# G021dec.net
KiCad netlist of a schematic drawn in EAGLE
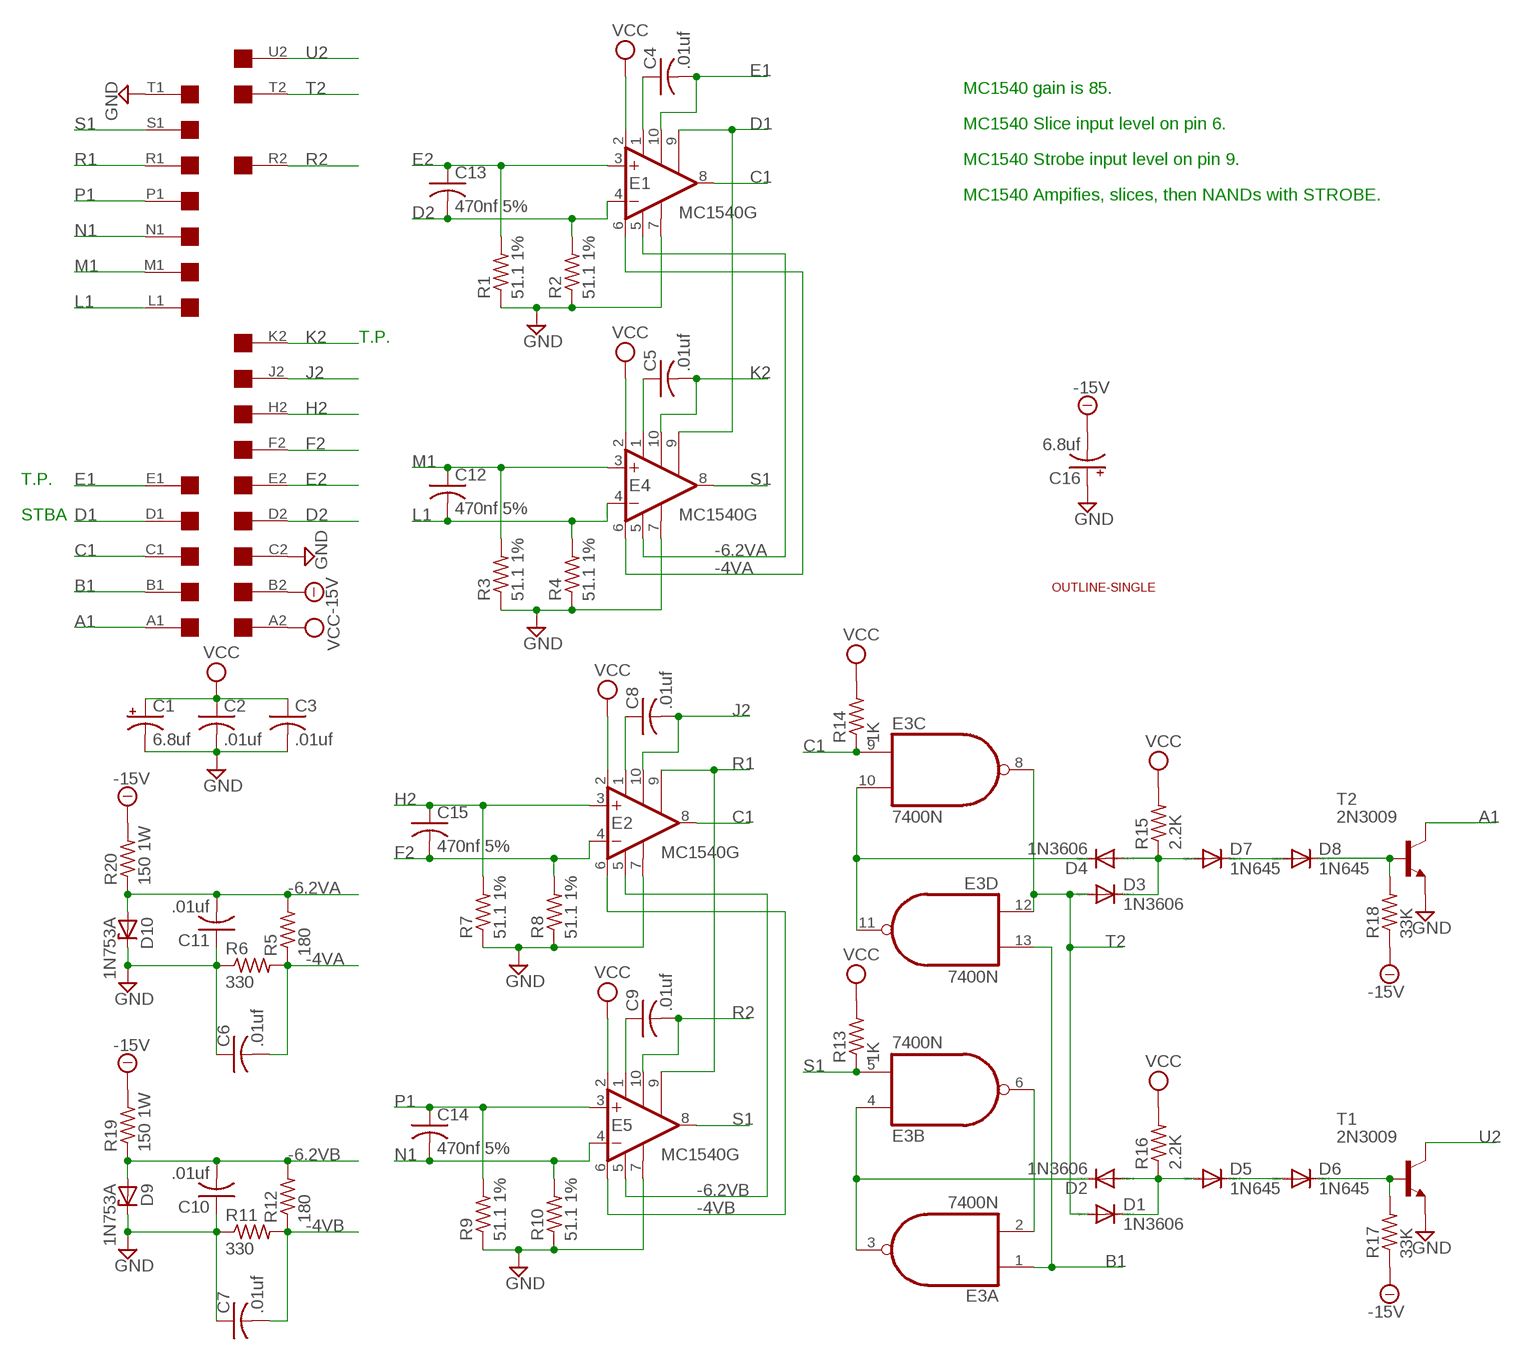
[diagram p0: schematic, sheet 1]

(export (version "E")
  (design (tool "Eeschema 10.0.6"))
  (components
    (comp (ref "C1")
      (value "6.8uf")
      (footprint "eagle-import:E15-5")
      (libsource (lib "eagle-import") (part "CPOL-USE15-5AXIAL"))
    )
    (comp (ref "C2")
      (value ".01uf")
      (footprint "eagle-import:C050-025X075")
      (libsource (lib "eagle-import") (part "C-US050-025X075"))
    )
    (comp (ref "C3")
      (value ".01uf")
      (footprint "eagle-import:C050-025X075")
      (libsource (lib "eagle-import") (part "C-US050-025X075"))
    )
    (comp (ref "C4")
      (value ".01uf")
      (footprint "eagle-import:C050-025X075")
      (libsource (lib "eagle-import") (part "C-US050-025X075"))
    )
    (comp (ref "C5")
      (value ".01uf")
      (footprint "eagle-import:C050-025X075")
      (libsource (lib "eagle-import") (part "C-US050-025X075"))
    )
    (comp (ref "C6")
      (value ".01uf")
      (footprint "eagle-import:C050-025X075")
      (libsource (lib "eagle-import") (part "C-US050-025X075"))
    )
    (comp (ref "C7")
      (value ".01uf")
      (footprint "eagle-import:C050-025X075")
      (libsource (lib "eagle-import") (part "C-US050-025X075"))
    )
    (comp (ref "C8")
      (value ".01uf")
      (footprint "eagle-import:C050-025X075")
      (libsource (lib "eagle-import") (part "C-US050-025X075"))
    )
    (comp (ref "C9")
      (value ".01uf")
      (footprint "eagle-import:C050-025X075")
      (libsource (lib "eagle-import") (part "C-US050-025X075"))
    )
    (comp (ref "C10")
      (value ".01uf")
      (footprint "eagle-import:C050-025X075")
      (libsource (lib "eagle-import") (part "C-US050-025X075"))
    )
    (comp (ref "C11")
      (value ".01uf")
      (footprint "eagle-import:C050-025X075")
      (libsource (lib "eagle-import") (part "C-US050-025X075"))
    )
    (comp (ref "C12")
      (value "470nf 5%")
      (footprint "eagle-import:C050-025X075")
      (libsource (lib "eagle-import") (part "C-US050-025X075"))
    )
    (comp (ref "C13")
      (value "470nf 5%")
      (footprint "eagle-import:C050-025X075")
      (libsource (lib "eagle-import") (part "C-US050-025X075"))
    )
    (comp (ref "C14")
      (value "470nf 5%")
      (footprint "eagle-import:C050-025X075")
      (libsource (lib "eagle-import") (part "C-US050-025X075"))
    )
    (comp (ref "C15")
      (value "470nf 5%")
      (footprint "eagle-import:C050-025X075")
      (libsource (lib "eagle-import") (part "C-US050-025X075"))
    )
    (comp (ref "C16")
      (value "6.8uf")
      (footprint "eagle-import:E15-5")
      (libsource (lib "eagle-import") (part "CPOL-USE15-5AXIAL"))
    )
    (comp (ref "D1")
      (value "1N3606")
      (footprint "eagle-import:DO35-10")
      (libsource (lib "eagle-import") (part "1N4148DO35-10"))
    )
    (comp (ref "D2")
      (value "1N3606")
      (footprint "eagle-import:DO35-10")
      (libsource (lib "eagle-import") (part "1N4148DO35-10"))
    )
    (comp (ref "D3")
      (value "1N3606")
      (footprint "eagle-import:DO35-10")
      (libsource (lib "eagle-import") (part "1N4148DO35-10"))
    )
    (comp (ref "D4")
      (value "1N3606")
      (footprint "eagle-import:DO35-10")
      (libsource (lib "eagle-import") (part "1N4148DO35-10"))
    )
    (comp (ref "D5")
      (value "1N645")
      (footprint "eagle-import:DO35-10")
      (libsource (lib "eagle-import") (part "1N4148DO35-10"))
    )
    (comp (ref "D6")
      (value "1N645")
      (footprint "eagle-import:DO35-10")
      (libsource (lib "eagle-import") (part "1N4148DO35-10"))
    )
    (comp (ref "D7")
      (value "1N645")
      (footprint "eagle-import:DO35-10")
      (libsource (lib "eagle-import") (part "1N4148DO35-10"))
    )
    (comp (ref "D8")
      (value "1N645")
      (footprint "eagle-import:DO35-10")
      (libsource (lib "eagle-import") (part "1N4148DO35-10"))
    )
    (comp (ref "D9")
      (value "1N753A")
      (footprint "eagle-import:F126Z10")
      (libsource (lib "eagle-import") (part "ZENER-DIODEF126-10"))
    )
    (comp (ref "D10")
      (value "1N753A")
      (footprint "eagle-import:F126Z10")
      (libsource (lib "eagle-import") (part "ZENER-DIODEF126-10"))
    )
    (comp (ref "E1")
      (value "MC1540G")
      (footprint "eagle-import:602B")
      (libsource (lib "eagle-import") (part "MC1540G"))
    )
    (comp (ref "E2")
      (value "MC1540G")
      (footprint "eagle-import:602B")
      (libsource (lib "eagle-import") (part "MC1540G"))
    )
    (comp (ref "E3")
      (value "7400N")
      (footprint "eagle-import:DIL14")
      (libsource (lib "eagle-import") (part "7400N"))
    )
    (comp (ref "E4")
      (value "MC1540G")
      (footprint "eagle-import:602B")
      (libsource (lib "eagle-import") (part "MC1540G"))
    )
    (comp (ref "E5")
      (value "MC1540G")
      (footprint "eagle-import:602B")
      (libsource (lib "eagle-import") (part "MC1540G"))
    )
    (comp (ref "R1")
      (value "51.1 1%")
      (footprint "eagle-import:0207_10")
      (libsource (lib "eagle-import") (part "R-US_0207/10"))
    )
    (comp (ref "R2")
      (value "51.1 1%")
      (footprint "eagle-import:0207_10")
      (libsource (lib "eagle-import") (part "R-US_0207/10"))
    )
    (comp (ref "R3")
      (value "51.1 1%")
      (footprint "eagle-import:0207_10")
      (libsource (lib "eagle-import") (part "R-US_0207/10"))
    )
    (comp (ref "R4")
      (value "51.1 1%")
      (footprint "eagle-import:0207_10")
      (libsource (lib "eagle-import") (part "R-US_0207/10"))
    )
    (comp (ref "R5")
      (value "180")
      (footprint "eagle-import:0207_10")
      (libsource (lib "eagle-import") (part "R-US_0207/10"))
    )
    (comp (ref "R6")
      (value "330")
      (footprint "eagle-import:0207_10")
      (libsource (lib "eagle-import") (part "R-US_0207/10"))
    )
    (comp (ref "R7")
      (value "51.1 1%")
      (footprint "eagle-import:0207_10")
      (libsource (lib "eagle-import") (part "R-US_0207/10"))
    )
    (comp (ref "R8")
      (value "51.1 1%")
      (footprint "eagle-import:0207_10")
      (libsource (lib "eagle-import") (part "R-US_0207/10"))
    )
    (comp (ref "R9")
      (value "51.1 1%")
      (footprint "eagle-import:0207_10")
      (libsource (lib "eagle-import") (part "R-US_0207/10"))
    )
    (comp (ref "R10")
      (value "51.1 1%")
      (footprint "eagle-import:0207_10")
      (libsource (lib "eagle-import") (part "R-US_0207/10"))
    )
    (comp (ref "R11")
      (value "330")
      (footprint "eagle-import:0207_10")
      (libsource (lib "eagle-import") (part "R-US_0207/10"))
    )
    (comp (ref "R12")
      (value "180")
      (footprint "eagle-import:0207_10")
      (libsource (lib "eagle-import") (part "R-US_0207/10"))
    )
    (comp (ref "R13")
      (value "1K")
      (footprint "eagle-import:0207_10")
      (libsource (lib "eagle-import") (part "R-US_0207/10"))
    )
    (comp (ref "R14")
      (value "1K")
      (footprint "eagle-import:0207_10")
      (libsource (lib "eagle-import") (part "R-US_0207/10"))
    )
    (comp (ref "R15")
      (value "2.2K")
      (footprint "eagle-import:0207_10")
      (libsource (lib "eagle-import") (part "R-US_0207/10"))
    )
    (comp (ref "R16")
      (value "2.2K")
      (footprint "eagle-import:0207_10")
      (libsource (lib "eagle-import") (part "R-US_0207/10"))
    )
    (comp (ref "R17")
      (value "33K")
      (footprint "eagle-import:0207_10")
      (libsource (lib "eagle-import") (part "R-US_0207/10"))
    )
    (comp (ref "R18")
      (value "33K")
      (footprint "eagle-import:0207_10")
      (libsource (lib "eagle-import") (part "R-US_0207/10"))
    )
    (comp (ref "R19")
      (value "150 1W")
      (footprint "eagle-import:0414_15")
      (libsource (lib "eagle-import") (part "R-US_0414/15"))
    )
    (comp (ref "R20")
      (value "150 1W")
      (footprint "eagle-import:0414_15")
      (libsource (lib "eagle-import") (part "R-US_0414/15"))
    )
    (comp (ref "T1")
      (value "2N3009")
      (footprint "eagle-import:TO92")
      (libsource (lib "eagle-import") (part "2N3565"))
    )
    (comp (ref "T2")
      (value "2N3009")
      (footprint "eagle-import:TO92")
      (libsource (lib "eagle-import") (part "2N3565"))
    )
    (comp (ref "U$1")
      (value "SINGLE")
      (footprint "eagle-import:EDGE-CON2")
      (libsource (lib "eagle-import") (part "SINGLE"))
    )
    (comp (ref "U$2")
      (value "OUTLINE-SINGLE")
      (footprint "eagle-import:SINGLE")
      (libsource (lib "eagle-import") (part "OUTLINE-SINGLE"))
    )
  )
  (nets
    (net (code "1") (name "-15V") (class "Default")
      (node (ref "C16") (pin "-") (pinfunction "-_-") (pintype "passive"))
      (node (ref "R17") (pin "1") (pinfunction "1_1") (pintype "passive"))
      (node (ref "R18") (pin "1") (pinfunction "1_1") (pintype "passive"))
      (node (ref "R19") (pin "2") (pinfunction "2_2") (pintype "passive"))
      (node (ref "R20") (pin "2") (pinfunction "2_2") (pintype "passive"))
      (node (ref "U$1") (pin "B2") (pinfunction "1_B2") (pintype "bidirectional"))
    )
    (net (code "2") (name "/-4VA") (class "Default")
      (node (ref "C6") (pin "2") (pinfunction "2_2") (pintype "passive"))
      (node (ref "E1") (pin "6") (pinfunction "SLICE_6") (pintype "bidirectional"))
      (node (ref "E4") (pin "6") (pinfunction "SLICE_6") (pintype "bidirectional"))
      (node (ref "R5") (pin "1") (pinfunction "1_1") (pintype "passive"))
      (node (ref "R6") (pin "2") (pinfunction "2_2") (pintype "passive"))
    )
    (net (code "3") (name "/-4VB") (class "Default")
      (node (ref "C7") (pin "2") (pinfunction "2_2") (pintype "passive"))
      (node (ref "E2") (pin "6") (pinfunction "SLICE_6") (pintype "bidirectional"))
      (node (ref "E5") (pin "6") (pinfunction "SLICE_6") (pintype "bidirectional"))
      (node (ref "R11") (pin "2") (pinfunction "2_2") (pintype "passive"))
      (node (ref "R12") (pin "1") (pinfunction "1_1") (pintype "passive"))
    )
    (net (code "4") (name "/-6.2VA") (class "Default")
      (node (ref "C11") (pin "2") (pinfunction "2_2") (pintype "passive"))
      (node (ref "D10") (pin "A") (pinfunction "A_A") (pintype "passive"))
      (node (ref "E1") (pin "5") (pinfunction "V-_5") (pintype "power_in"))
      (node (ref "E4") (pin "5") (pinfunction "V-_5") (pintype "power_in"))
      (node (ref "R20") (pin "1") (pinfunction "1_1") (pintype "passive"))
      (node (ref "R5") (pin "2") (pinfunction "2_2") (pintype "passive"))
    )
    (net (code "5") (name "/-6.2VB") (class "Default")
      (node (ref "C10") (pin "2") (pinfunction "2_2") (pintype "passive"))
      (node (ref "D9") (pin "A") (pinfunction "A_A") (pintype "passive"))
      (node (ref "E2") (pin "5") (pinfunction "V-_5") (pintype "power_in"))
      (node (ref "E5") (pin "5") (pinfunction "V-_5") (pintype "power_in"))
      (node (ref "R12") (pin "2") (pinfunction "2_2") (pintype "passive"))
      (node (ref "R19") (pin "1") (pinfunction "1_1") (pintype "passive"))
    )
    (net (code "6") (name "/A1") (class "Default")
      (node (ref "T2") (pin "1") (pinfunction "C_1") (pintype "passive"))
      (node (ref "U$1") (pin "A1") (pinfunction "1_A1") (pintype "bidirectional"))
    )
    (net (code "7") (name "/B1") (class "Default")
      (node (ref "E3") (pin "1") (pinfunction "I0_1") (pintype "input"))
      (node (ref "E3") (pin "13") (pinfunction "I1_13") (pintype "input"))
      (node (ref "U$1") (pin "B1") (pinfunction "1_B1") (pintype "bidirectional"))
    )
    (net (code "8") (name "/C1") (class "Default")
      (node (ref "E1") (pin "8") (pinfunction "OUT_8") (pintype "open_collector"))
      (node (ref "E2") (pin "8") (pinfunction "OUT_8") (pintype "open_collector"))
      (node (ref "E3") (pin "9") (pinfunction "I0_9") (pintype "input"))
      (node (ref "R14") (pin "1") (pinfunction "1_1") (pintype "passive"))
      (node (ref "U$1") (pin "C1") (pinfunction "1_C1") (pintype "bidirectional"))
    )
    (net (code "9") (name "/D1") (class "Default")
      (node (ref "E1") (pin "9") (pinfunction "ISTROBE_9") (pintype "passive"))
      (node (ref "E4") (pin "9") (pinfunction "ISTROBE_9") (pintype "passive"))
      (node (ref "U$1") (pin "D1") (pinfunction "1_D1") (pintype "bidirectional"))
    )
    (net (code "10") (name "/D2") (class "Default")
      (node (ref "C13") (pin "2") (pinfunction "2_2") (pintype "passive"))
      (node (ref "E1") (pin "4") (pinfunction "-IN_4") (pintype "input"))
      (node (ref "R2") (pin "2") (pinfunction "2_2") (pintype "passive"))
      (node (ref "U$1") (pin "D2") (pinfunction "1_D2") (pintype "bidirectional"))
    )
    (net (code "11") (name "/E1") (class "Default")
      (node (ref "C4") (pin "2") (pinfunction "2_2") (pintype "passive"))
      (node (ref "E1") (pin "10") (pinfunction "CEXTB_10") (pintype "passive"))
      (node (ref "U$1") (pin "E1") (pinfunction "1_E1") (pintype "bidirectional"))
    )
    (net (code "12") (name "/E2") (class "Default")
      (node (ref "C13") (pin "1") (pinfunction "1_1") (pintype "passive"))
      (node (ref "E1") (pin "3") (pinfunction "+IN_3") (pintype "input"))
      (node (ref "R1") (pin "2") (pinfunction "2_2") (pintype "passive"))
      (node (ref "U$1") (pin "E2") (pinfunction "1_E2") (pintype "bidirectional"))
    )
    (net (code "13") (name "/F2") (class "Default")
      (node (ref "C15") (pin "2") (pinfunction "2_2") (pintype "passive"))
      (node (ref "E2") (pin "4") (pinfunction "-IN_4") (pintype "input"))
      (node (ref "R8") (pin "2") (pinfunction "2_2") (pintype "passive"))
      (node (ref "U$1") (pin "F2") (pinfunction "1_F2") (pintype "bidirectional"))
    )
    (net (code "14") (name "/H2") (class "Default")
      (node (ref "C15") (pin "1") (pinfunction "1_1") (pintype "passive"))
      (node (ref "E2") (pin "3") (pinfunction "+IN_3") (pintype "input"))
      (node (ref "R7") (pin "2") (pinfunction "2_2") (pintype "passive"))
      (node (ref "U$1") (pin "H2") (pinfunction "1_H2") (pintype "bidirectional"))
    )
    (net (code "15") (name "/J2") (class "Default")
      (node (ref "C8") (pin "2") (pinfunction "2_2") (pintype "passive"))
      (node (ref "E2") (pin "10") (pinfunction "CEXTB_10") (pintype "passive"))
      (node (ref "U$1") (pin "J2") (pinfunction "1_J2") (pintype "bidirectional"))
    )
    (net (code "16") (name "/K2") (class "Default")
      (node (ref "C5") (pin "2") (pinfunction "2_2") (pintype "passive"))
      (node (ref "E4") (pin "10") (pinfunction "CEXTB_10") (pintype "passive"))
      (node (ref "U$1") (pin "K2") (pinfunction "1_K2") (pintype "bidirectional"))
    )
    (net (code "17") (name "/L1") (class "Default")
      (node (ref "C12") (pin "2") (pinfunction "2_2") (pintype "passive"))
      (node (ref "E4") (pin "4") (pinfunction "-IN_4") (pintype "input"))
      (node (ref "R4") (pin "2") (pinfunction "2_2") (pintype "passive"))
      (node (ref "U$1") (pin "L1") (pinfunction "1_L1") (pintype "bidirectional"))
    )
    (net (code "18") (name "/M1") (class "Default")
      (node (ref "C12") (pin "1") (pinfunction "1_1") (pintype "passive"))
      (node (ref "E4") (pin "3") (pinfunction "+IN_3") (pintype "input"))
      (node (ref "R3") (pin "2") (pinfunction "2_2") (pintype "passive"))
      (node (ref "U$1") (pin "M1") (pinfunction "1_M1") (pintype "bidirectional"))
    )
    (net (code "19") (name "/N1") (class "Default")
      (node (ref "C14") (pin "2") (pinfunction "2_2") (pintype "passive"))
      (node (ref "E5") (pin "4") (pinfunction "-IN_4") (pintype "input"))
      (node (ref "R10") (pin "2") (pinfunction "2_2") (pintype "passive"))
      (node (ref "U$1") (pin "N1") (pinfunction "1_N1") (pintype "bidirectional"))
    )
    (net (code "20") (name "/P1") (class "Default")
      (node (ref "C14") (pin "1") (pinfunction "1_1") (pintype "passive"))
      (node (ref "E5") (pin "3") (pinfunction "+IN_3") (pintype "input"))
      (node (ref "R9") (pin "2") (pinfunction "2_2") (pintype "passive"))
      (node (ref "U$1") (pin "P1") (pinfunction "1_P1") (pintype "bidirectional"))
    )
    (net (code "21") (name "/R1") (class "Default")
      (node (ref "E2") (pin "9") (pinfunction "ISTROBE_9") (pintype "passive"))
      (node (ref "E5") (pin "9") (pinfunction "ISTROBE_9") (pintype "passive"))
      (node (ref "U$1") (pin "R1") (pinfunction "1_R1") (pintype "bidirectional"))
    )
    (net (code "22") (name "/R2") (class "Default")
      (node (ref "C9") (pin "2") (pinfunction "2_2") (pintype "passive"))
      (node (ref "E5") (pin "10") (pinfunction "CEXTB_10") (pintype "passive"))
      (node (ref "U$1") (pin "R2") (pinfunction "1_R2") (pintype "bidirectional"))
    )
    (net (code "23") (name "/S1") (class "Default")
      (node (ref "E3") (pin "5") (pinfunction "I1_5") (pintype "input"))
      (node (ref "E4") (pin "8") (pinfunction "OUT_8") (pintype "open_collector"))
      (node (ref "E5") (pin "8") (pinfunction "OUT_8") (pintype "open_collector"))
      (node (ref "R13") (pin "1") (pinfunction "1_1") (pintype "passive"))
      (node (ref "U$1") (pin "S1") (pinfunction "1_S1") (pintype "bidirectional"))
    )
    (net (code "24") (name "/T2") (class "Default")
      (node (ref "D1") (pin "A") (pinfunction "A_A") (pintype "passive"))
      (node (ref "D3") (pin "A") (pinfunction "A_A") (pintype "passive"))
      (node (ref "E3") (pin "12") (pinfunction "I0_12") (pintype "input"))
      (node (ref "E3") (pin "8") (pinfunction "O_8") (pintype "output"))
      (node (ref "U$1") (pin "T2") (pinfunction "1_T2") (pintype "bidirectional"))
    )
    (net (code "25") (name "/U2") (class "Default")
      (node (ref "T1") (pin "1") (pinfunction "C_1") (pintype "passive"))
      (node (ref "U$1") (pin "U2") (pinfunction "1_U2") (pintype "bidirectional"))
    )
    (net (code "26") (name "GND") (class "Default")
      (node (ref "C1") (pin "-") (pinfunction "-_-") (pintype "passive"))
      (node (ref "C10") (pin "1") (pinfunction "1_1") (pintype "passive"))
      (node (ref "C11") (pin "1") (pinfunction "1_1") (pintype "passive"))
      (node (ref "C16") (pin "+") (pinfunction "+_+") (pintype "passive"))
      (node (ref "C2") (pin "2") (pinfunction "2_2") (pintype "passive"))
      (node (ref "C3") (pin "2") (pinfunction "2_2") (pintype "passive"))
      (node (ref "C6") (pin "1") (pinfunction "1_1") (pintype "passive"))
      (node (ref "C7") (pin "1") (pinfunction "1_1") (pintype "passive"))
      (node (ref "D10") (pin "C") (pinfunction "C_C") (pintype "passive"))
      (node (ref "D9") (pin "C") (pinfunction "C_C") (pintype "passive"))
      (node (ref "E1") (pin "7") (pinfunction "GND_7") (pintype "power_in"))
      (node (ref "E2") (pin "7") (pinfunction "GND_7") (pintype "power_in"))
      (node (ref "E4") (pin "7") (pinfunction "GND_7") (pintype "power_in"))
      (node (ref "E5") (pin "7") (pinfunction "GND_7") (pintype "power_in"))
      (node (ref "R1") (pin "1") (pinfunction "1_1") (pintype "passive"))
      (node (ref "R10") (pin "1") (pinfunction "1_1") (pintype "passive"))
      (node (ref "R11") (pin "1") (pinfunction "1_1") (pintype "passive"))
      (node (ref "R2") (pin "1") (pinfunction "1_1") (pintype "passive"))
      (node (ref "R3") (pin "1") (pinfunction "1_1") (pintype "passive"))
      (node (ref "R4") (pin "1") (pinfunction "1_1") (pintype "passive"))
      (node (ref "R6") (pin "1") (pinfunction "1_1") (pintype "passive"))
      (node (ref "R7") (pin "1") (pinfunction "1_1") (pintype "passive"))
      (node (ref "R8") (pin "1") (pinfunction "1_1") (pintype "passive"))
      (node (ref "R9") (pin "1") (pinfunction "1_1") (pintype "passive"))
      (node (ref "T1") (pin "3") (pinfunction "E_3") (pintype "passive"))
      (node (ref "T2") (pin "3") (pinfunction "E_3") (pintype "passive"))
      (node (ref "U$1") (pin "C2") (pinfunction "1_C2") (pintype "bidirectional"))
      (node (ref "U$1") (pin "T1") (pinfunction "1_T1") (pintype "bidirectional"))
    )
    (net (code "27") (name "Net-(D1-PadC)") (class "Default")
      (node (ref "D1") (pin "C") (pinfunction "C_C") (pintype "passive"))
      (node (ref "D2") (pin "A") (pinfunction "A_A") (pintype "passive"))
      (node (ref "D5") (pin "A") (pinfunction "A_A") (pintype "passive"))
      (node (ref "R16") (pin "1") (pinfunction "1_1") (pintype "passive"))
    )
    (net (code "28") (name "Net-(D3-PadC)") (class "Default")
      (node (ref "D3") (pin "C") (pinfunction "C_C") (pintype "passive"))
      (node (ref "D4") (pin "A") (pinfunction "A_A") (pintype "passive"))
      (node (ref "D7") (pin "A") (pinfunction "A_A") (pintype "passive"))
      (node (ref "R15") (pin "1") (pinfunction "1_1") (pintype "passive"))
    )
    (net (code "29") (name "Net-(D5-PadC)") (class "Default")
      (node (ref "D5") (pin "C") (pinfunction "C_C") (pintype "passive"))
      (node (ref "D6") (pin "A") (pinfunction "A_A") (pintype "passive"))
    )
    (net (code "30") (name "Net-(D7-PadC)") (class "Default")
      (node (ref "D7") (pin "C") (pinfunction "C_C") (pintype "passive"))
      (node (ref "D8") (pin "A") (pinfunction "A_A") (pintype "passive"))
    )
    (net (code "31") (name "Net-(E1-CEXTA)") (class "Default")
      (node (ref "C4") (pin "1") (pinfunction "1_1") (pintype "passive"))
      (node (ref "E1") (pin "1") (pinfunction "CEXTA_1") (pintype "passive"))
    )
    (net (code "32") (name "Net-(E2-CEXTA)") (class "Default")
      (node (ref "C8") (pin "1") (pinfunction "1_1") (pintype "passive"))
      (node (ref "E2") (pin "1") (pinfunction "CEXTA_1") (pintype "passive"))
    )
    (net (code "33") (name "Net-(E3A-I1)") (class "Default")
      (node (ref "E3") (pin "2") (pinfunction "I1_2") (pintype "input"))
      (node (ref "E3") (pin "6") (pinfunction "O_6") (pintype "output"))
    )
    (net (code "34") (name "Net-(E3A-O)") (class "Default")
      (node (ref "D2") (pin "C") (pinfunction "C_C") (pintype "passive"))
      (node (ref "E3") (pin "3") (pinfunction "O_3") (pintype "output"))
      (node (ref "E3") (pin "4") (pinfunction "I0_4") (pintype "input"))
    )
    (net (code "35") (name "Net-(E3C-I1)") (class "Default")
      (node (ref "D4") (pin "C") (pinfunction "C_C") (pintype "passive"))
      (node (ref "E3") (pin "10") (pinfunction "I1_10") (pintype "input"))
      (node (ref "E3") (pin "11") (pinfunction "O_11") (pintype "output"))
    )
    (net (code "36") (name "Net-(E4-CEXTA)") (class "Default")
      (node (ref "C5") (pin "1") (pinfunction "1_1") (pintype "passive"))
      (node (ref "E4") (pin "1") (pinfunction "CEXTA_1") (pintype "passive"))
    )
    (net (code "37") (name "Net-(E5-CEXTA)") (class "Default")
      (node (ref "C9") (pin "1") (pinfunction "1_1") (pintype "passive"))
      (node (ref "E5") (pin "1") (pinfunction "CEXTA_1") (pintype "passive"))
    )
    (net (code "38") (name "Net-(T1-B)") (class "Default")
      (node (ref "D6") (pin "C") (pinfunction "C_C") (pintype "passive"))
      (node (ref "R17") (pin "2") (pinfunction "2_2") (pintype "passive"))
      (node (ref "T1") (pin "2") (pinfunction "B_2") (pintype "passive"))
    )
    (net (code "39") (name "Net-(T2-B)") (class "Default")
      (node (ref "D8") (pin "C") (pinfunction "C_C") (pintype "passive"))
      (node (ref "R18") (pin "2") (pinfunction "2_2") (pintype "passive"))
      (node (ref "T2") (pin "2") (pinfunction "B_2") (pintype "passive"))
    )
    (net (code "40") (name "VCC") (class "Default")
      (node (ref "C1") (pin "+") (pinfunction "+_+") (pintype "passive"))
      (node (ref "C2") (pin "1") (pinfunction "1_1") (pintype "passive"))
      (node (ref "C3") (pin "1") (pinfunction "1_1") (pintype "passive"))
      (node (ref "E1") (pin "2") (pinfunction "V+_2") (pintype "power_in"))
      (node (ref "E2") (pin "2") (pinfunction "V+_2") (pintype "power_in"))
      (node (ref "E4") (pin "2") (pinfunction "V+_2") (pintype "power_in"))
      (node (ref "E5") (pin "2") (pinfunction "V+_2") (pintype "power_in"))
      (node (ref "R13") (pin "2") (pinfunction "2_2") (pintype "passive"))
      (node (ref "R14") (pin "2") (pinfunction "2_2") (pintype "passive"))
      (node (ref "R15") (pin "2") (pinfunction "2_2") (pintype "passive"))
      (node (ref "R16") (pin "2") (pinfunction "2_2") (pintype "passive"))
      (node (ref "U$1") (pin "A2") (pinfunction "1_A2") (pintype "bidirectional"))
    )
  )
)
